# Mini-RS485_RJ45-MySens-v05.net
KiCad netlist of a schematic drawn in EAGLE
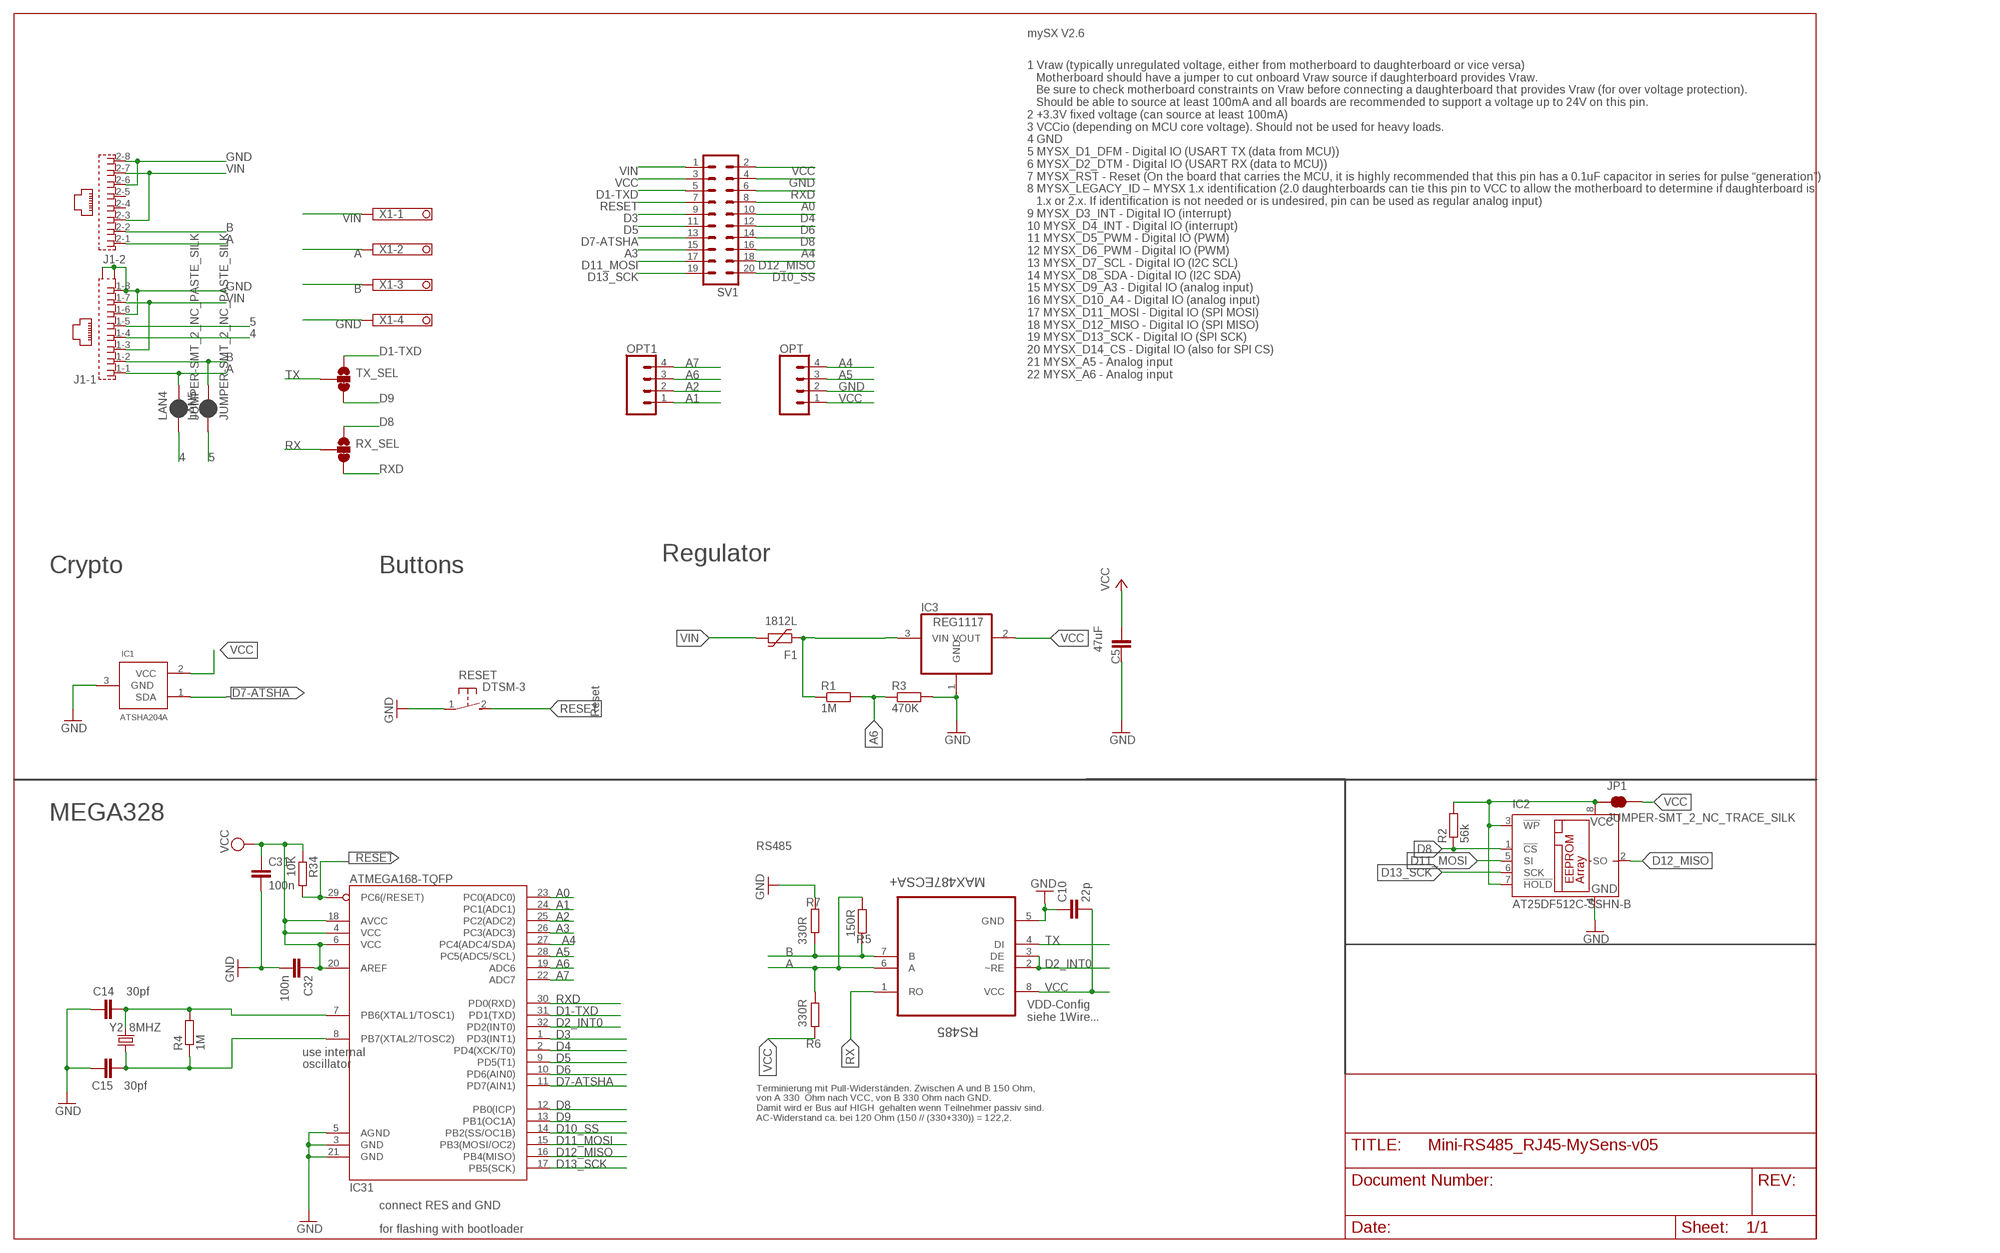
[diagram p0: schematic, sheet 1]

(export (version "E")
  (design (tool "Eeschema 10.0.6"))
  (components
    (comp (ref "C5")
      (value "47uF")
      (footprint "eagle-import:C1210")
      (libsource (lib "eagle-import") (part "C-EUC1210"))
    )
    (comp (ref "C10")
      (value "22p")
      (footprint "eagle-import:C0805")
      (libsource (lib "eagle-import") (part "C-EUC0805"))
    )
    (comp (ref "C14")
      (value "30pf")
      (footprint "eagle-import:0805")
      (libsource (lib "eagle-import") (part "CAP0805"))
    )
    (comp (ref "C15")
      (value "30pf")
      (footprint "eagle-import:0805")
      (libsource (lib "eagle-import") (part "CAP0805"))
    )
    (comp (ref "C31")
      (value "100n")
      (footprint "eagle-import:C0805")
      (libsource (lib "eagle-import") (part "C-EUC0805"))
    )
    (comp (ref "C32")
      (value "100n")
      (footprint "eagle-import:C0805")
      (libsource (lib "eagle-import") (part "C-EUC0805"))
    )
    (comp (ref "F1")
      (value "1812L")
      (footprint "eagle-import:1812L")
      (libsource (lib "eagle-import") (part "1812L"))
    )
    (comp (ref "IC1")
      (value "ATSHA204A")
      (footprint "eagle-import:SOT23")
      (libsource (lib "eagle-import") (part "ATSHA204A"))
    )
    (comp (ref "IC2")
      (value "AT25DF512C-SSHN-B")
      (footprint "eagle-import:SO-08")
      (fields (field (name "MF") "MICROCHIP") (field (name "MPN") "25AA080/SN"))
      (libsource (lib "eagle-import") (part "25SNAA080"))
    )
    (comp (ref "IC3")
      (value "REG1117")
      (footprint "eagle-import:SOT223")
      (libsource (lib "eagle-import") (part "REG1117"))
    )
    (comp (ref "IC31")
      (value "ATMEGA168-TQFP")
      (footprint "eagle-import:TQFP32-08")
      (libsource (lib "eagle-import") (part "ATMEGA168-TQFP"))
    )
    (comp (ref "J1")
      (value "RJ45_2X_NARROW_SHILDPINS")
      (footprint "eagle-import:RJ45_2X_NARROW_SHILDPINS")
      (libsource (lib "eagle-import") (part "RJ45_2X_NARROW_SHILDPINS"))
    )
    (comp (ref "JP1")
      (value "JUMPER-SMT_2_NC_TRACE_SILK")
      (footprint "eagle-import:SMT-JUMPER_2_NC_TRACE_SILK")
      (libsource (lib "eagle-import") (part "JUMPER-SMT_2_NC_TRACE_SILK"))
    )
    (comp (ref "LAN4")
      (value "JUMPER-SMT_2_NC_PASTE_SILK")
      (footprint "eagle-import:SMT-JUMPER_2_NC_PASTE_SILK")
      (libsource (lib "eagle-import") (part "JUMPER-SMT_2_NC_PASTE_SILK"))
    )
    (comp (ref "LAN5")
      (value "JUMPER-SMT_2_NC_PASTE_SILK")
      (footprint "eagle-import:SMT-JUMPER_2_NC_PASTE_SILK")
      (libsource (lib "eagle-import") (part "JUMPER-SMT_2_NC_PASTE_SILK"))
    )
    (comp (ref "OPT")
      (value "CONN_04")
      (footprint "eagle-import:1X04")
      (libsource (lib "eagle-import") (part "CONN_04"))
    )
    (comp (ref "OPT1")
      (value "CONN_04")
      (footprint "eagle-import:1X04")
      (libsource (lib "eagle-import") (part "CONN_04"))
    )
    (comp (ref "R1")
      (value "1M")
      (footprint "eagle-import:M0805")
      (libsource (lib "eagle-import") (part "R-EU_M0805"))
    )
    (comp (ref "R2")
      (value "56k")
      (footprint "eagle-import:M0805")
      (libsource (lib "eagle-import") (part "resistor_R-EU_M0805"))
    )
    (comp (ref "R3")
      (value "470K")
      (footprint "eagle-import:R0805")
      (libsource (lib "eagle-import") (part "R-EU_R0805"))
    )
    (comp (ref "R4")
      (value "1M")
      (footprint "eagle-import:M0805")
      (libsource (lib "eagle-import") (part "R-EU_M0805"))
    )
    (comp (ref "R5")
      (value "150R")
      (footprint "eagle-import:R0805")
      (libsource (lib "eagle-import") (part "R-EU_R0805"))
    )
    (comp (ref "R6")
      (value "330R")
      (footprint "eagle-import:R0805")
      (libsource (lib "eagle-import") (part "R-EU_R0805"))
    )
    (comp (ref "R7")
      (value "330R")
      (footprint "eagle-import:R0805")
      (libsource (lib "eagle-import") (part "R-EU_R0805"))
    )
    (comp (ref "R34")
      (value "10K")
      (footprint "eagle-import:R0805")
      (libsource (lib "eagle-import") (part "R-EU_R0805"))
    )
    (comp (ref "RESET")
      (value "DTSM-3")
      (footprint "eagle-import:DTSM-3")
      (libsource (lib "eagle-import") (part "DTSM-3"))
    )
    (comp (ref "RS485")
      (value "MAX487ECSA+")
      (footprint "eagle-import:SOIC127P600X175-8N")
      (libsource (lib "eagle-import") (part "MAX487ECSA+"))
    )
    (comp (ref "RX_SEL")
      (value "JUMPER-SMT_3_1-NC_TRACE_SILK")
      (footprint "eagle-import:SMT-JUMPER_3_1-NC_TRACE_SILK")
      (libsource (lib "eagle-import") (part "JUMPER-SMT_3_1-NC_TRACE_SILK"))
    )
    (comp (ref "SV1")
      (value "MA10-2")
      (footprint "eagle-import:MA10-2")
      (libsource (lib "eagle-import") (part "MA10-2"))
    )
    (comp (ref "TX_SEL")
      (value "JUMPER-SMT_3_1-NC_TRACE_SILK")
      (footprint "eagle-import:SMT-JUMPER_3_1-NC_TRACE_SILK")
      (libsource (lib "eagle-import") (part "JUMPER-SMT_3_1-NC_TRACE_SILK"))
    )
    (comp (ref "X1")
      (value "1751264")
      (footprint "eagle-import:1751264")
      (libsource (lib "eagle-import") (part "1751264"))
    )
    (comp (ref "Y2")
      (value "8MHZ")
      (footprint "eagle-import:CRYSTAL-TXC-7A")
      (libsource (lib "eagle-import") (part "CRYSTALTXC-7A"))
    )
  )
  (nets
    (net (code "1") (name "/4") (class "Default")
      (node (ref "J1") (pin "1-4") (pinfunction "4_1-4") (pintype "passive"))
      (node (ref "LAN4") (pin "1") (pinfunction "1_1") (pintype "passive"))
    )
    (net (code "2") (name "/5") (class "Default")
      (node (ref "J1") (pin "1-5") (pinfunction "5_1-5") (pintype "passive"))
      (node (ref "LAN5") (pin "1") (pinfunction "1_1") (pintype "passive"))
    )
    (net (code "3") (name "/A") (class "Default")
      (node (ref "J1") (pin "1-1") (pinfunction "1_1-1") (pintype "passive"))
      (node (ref "J1") (pin "2-1") (pinfunction "1_2-1") (pintype "passive"))
      (node (ref "LAN4") (pin "2") (pinfunction "2_2") (pintype "passive"))
      (node (ref "R5") (pin "1") (pinfunction "1_1") (pintype "passive"))
      (node (ref "R6") (pin "2") (pinfunction "2_2") (pintype "passive"))
      (node (ref "RS485") (pin "6") (pinfunction "A_6") (pintype "bidirectional"))
      (node (ref "X1") (pin "2") (pinfunction "K_2") (pintype "passive"))
    )
    (net (code "4") (name "/A0") (class "Default")
      (node (ref "IC31") (pin "23") (pinfunction "PC0(ADC0)_23") (pintype "bidirectional"))
      (node (ref "SV1") (pin "8") (pinfunction "8_8") (pintype "passive"))
    )
    (net (code "5") (name "/A1") (class "Default")
      (node (ref "IC31") (pin "24") (pinfunction "PC1(ADC1)_24") (pintype "bidirectional"))
      (node (ref "OPT1") (pin "1") (pinfunction "1_1") (pintype "passive"))
    )
    (net (code "6") (name "/A2") (class "Default")
      (node (ref "IC31") (pin "25") (pinfunction "PC2(ADC2)_25") (pintype "bidirectional"))
      (node (ref "OPT1") (pin "2") (pinfunction "2_2") (pintype "passive"))
    )
    (net (code "7") (name "/A3") (class "Default")
      (node (ref "IC31") (pin "26") (pinfunction "PC3(ADC3)_26") (pintype "bidirectional"))
      (node (ref "SV1") (pin "15") (pinfunction "15_15") (pintype "passive"))
    )
    (net (code "8") (name "/A4") (class "Default")
      (node (ref "IC31") (pin "27") (pinfunction "PC4(ADC4/SDA)_27") (pintype "bidirectional"))
      (node (ref "OPT") (pin "4") (pinfunction "4_4") (pintype "passive"))
      (node (ref "SV1") (pin "16") (pinfunction "16_16") (pintype "passive"))
    )
    (net (code "9") (name "/A5") (class "Default")
      (node (ref "IC31") (pin "28") (pinfunction "PC5(ADC5/SCL)_28") (pintype "bidirectional"))
      (node (ref "OPT") (pin "3") (pinfunction "3_3") (pintype "passive"))
    )
    (net (code "10") (name "/A7") (class "Default")
      (node (ref "IC31") (pin "22") (pinfunction "ADC7_22") (pintype "bidirectional"))
      (node (ref "OPT1") (pin "4") (pinfunction "4_4") (pintype "passive"))
    )
    (net (code "11") (name "/B") (class "Default")
      (node (ref "J1") (pin "1-2") (pinfunction "2_1-2") (pintype "passive"))
      (node (ref "J1") (pin "2-2") (pinfunction "2_2-2") (pintype "passive"))
      (node (ref "LAN5") (pin "2") (pinfunction "2_2") (pintype "passive"))
      (node (ref "R5") (pin "2") (pinfunction "2_2") (pintype "passive"))
      (node (ref "R7") (pin "1") (pinfunction "1_1") (pintype "passive"))
      (node (ref "RS485") (pin "7") (pinfunction "B_7") (pintype "bidirectional"))
      (node (ref "X1") (pin "3") (pinfunction "K_3") (pintype "passive"))
    )
    (net (code "12") (name "/D1-TXD") (class "Default")
      (node (ref "IC31") (pin "31") (pinfunction "PD1(TXD)_31") (pintype "bidirectional"))
      (node (ref "SV1") (pin "5") (pinfunction "5_5") (pintype "passive"))
      (node (ref "TX_SEL") (pin "1") (pinfunction "1_1") (pintype "passive"))
    )
    (net (code "13") (name "/D2_INT0") (class "Default")
      (node (ref "IC31") (pin "32") (pinfunction "PD2(INT0)_32") (pintype "bidirectional"))
      (node (ref "RS485") (pin "2") (pinfunction "~{RE}_2") (pintype "input"))
      (node (ref "RS485") (pin "3") (pinfunction "DE_3") (pintype "input"))
    )
    (net (code "14") (name "/D3") (class "Default")
      (node (ref "IC31") (pin "1") (pinfunction "PD3(INT1)_1") (pintype "bidirectional"))
      (node (ref "SV1") (pin "9") (pinfunction "9_9") (pintype "passive"))
    )
    (net (code "15") (name "/D4") (class "Default")
      (node (ref "IC31") (pin "2") (pinfunction "PD4(XCK/T0)_2") (pintype "bidirectional"))
      (node (ref "SV1") (pin "10") (pinfunction "10_10") (pintype "passive"))
    )
    (net (code "16") (name "/D5") (class "Default")
      (node (ref "IC31") (pin "9") (pinfunction "PD5(T1)_9") (pintype "bidirectional"))
      (node (ref "SV1") (pin "11") (pinfunction "11_11") (pintype "passive"))
    )
    (net (code "17") (name "/D6") (class "Default")
      (node (ref "IC31") (pin "10") (pinfunction "PD6(AIN0)_10") (pintype "bidirectional"))
      (node (ref "SV1") (pin "12") (pinfunction "12_12") (pintype "passive"))
    )
    (net (code "18") (name "/D7-ATSHA") (class "Default")
      (node (ref "IC1") (pin "1") (pinfunction "SDA_1") (pintype "bidirectional"))
      (node (ref "IC31") (pin "11") (pinfunction "PD7(AIN1)_11") (pintype "bidirectional"))
      (node (ref "SV1") (pin "13") (pinfunction "13_13") (pintype "passive"))
    )
    (net (code "19") (name "/D9") (class "Default")
      (node (ref "IC31") (pin "13") (pinfunction "PB1(OC1A)_13") (pintype "bidirectional"))
      (node (ref "TX_SEL") (pin "3") (pinfunction "3_3") (pintype "passive"))
    )
    (net (code "20") (name "/D10_SS") (class "Default")
      (node (ref "IC31") (pin "14") (pinfunction "PB2(SS/OC1B)_14") (pintype "bidirectional"))
      (node (ref "SV1") (pin "20") (pinfunction "20_20") (pintype "passive"))
    )
    (net (code "21") (name "/RXD") (class "Default")
      (node (ref "IC31") (pin "30") (pinfunction "PD0(RXD)_30") (pintype "bidirectional"))
      (node (ref "RX_SEL") (pin "3") (pinfunction "3_3") (pintype "passive"))
      (node (ref "SV1") (pin "6") (pinfunction "6_6") (pintype "passive"))
    )
    (net (code "22") (name "/TX") (class "Default")
      (node (ref "RS485") (pin "4") (pinfunction "DI_4") (pintype "input"))
      (node (ref "TX_SEL") (pin "2") (pinfunction "2_2") (pintype "passive"))
    )
    (net (code "23") (name "A6") (class "Default")
      (node (ref "IC31") (pin "19") (pinfunction "ADC6_19") (pintype "bidirectional"))
      (node (ref "OPT1") (pin "3") (pinfunction "3_3") (pintype "passive"))
      (node (ref "R1") (pin "2") (pinfunction "2_2") (pintype "passive"))
      (node (ref "R3") (pin "1") (pinfunction "1_1") (pintype "passive"))
    )
    (net (code "24") (name "D8") (class "Default")
      (node (ref "IC2") (pin "1") (pinfunction "~{CS}_1") (pintype "input"))
      (node (ref "IC31") (pin "12") (pinfunction "PB0(ICP)_12") (pintype "bidirectional"))
      (node (ref "R2") (pin "1") (pinfunction "1_1") (pintype "passive"))
      (node (ref "RX_SEL") (pin "1") (pinfunction "1_1") (pintype "passive"))
      (node (ref "SV1") (pin "14") (pinfunction "14_14") (pintype "passive"))
    )
    (net (code "25") (name "D11_MOSI") (class "Default")
      (node (ref "IC2") (pin "5") (pinfunction "SI_5") (pintype "input"))
      (node (ref "IC31") (pin "15") (pinfunction "PB3(MOSI/OC2)_15") (pintype "bidirectional"))
      (node (ref "SV1") (pin "17") (pinfunction "17_17") (pintype "passive"))
    )
    (net (code "26") (name "D12_MISO") (class "Default")
      (node (ref "IC2") (pin "2") (pinfunction "SO_2") (pintype "bidirectional"))
      (node (ref "IC31") (pin "16") (pinfunction "PB4(MISO)_16") (pintype "bidirectional"))
      (node (ref "SV1") (pin "18") (pinfunction "18_18") (pintype "passive"))
    )
    (net (code "27") (name "D13_SCK") (class "Default")
      (node (ref "IC2") (pin "6") (pinfunction "SCK_6") (pintype "input"))
      (node (ref "IC31") (pin "17") (pinfunction "PB5(SCK)_17") (pintype "bidirectional"))
      (node (ref "SV1") (pin "19") (pinfunction "19_19") (pintype "passive"))
    )
    (net (code "28") (name "GND") (class "Default")
      (node (ref "C10") (pin "1") (pinfunction "1_1") (pintype "passive"))
      (node (ref "C14") (pin "1") (pinfunction "1_1") (pintype "passive"))
      (node (ref "C15") (pin "1") (pinfunction "1_1") (pintype "passive"))
      (node (ref "C31") (pin "2") (pinfunction "2_2") (pintype "passive"))
      (node (ref "C32") (pin "2") (pinfunction "2_2") (pintype "passive"))
      (node (ref "C5") (pin "1") (pinfunction "1_1") (pintype "passive"))
      (node (ref "IC1") (pin "3") (pinfunction "GND_3") (pintype "bidirectional"))
      (node (ref "IC2") (pin "4") (pinfunction "GND_4") (pintype "power_in"))
      (node (ref "IC3") (pin "1") (pinfunction "GND_1") (pintype "power_in"))
      (node (ref "IC31") (pin "21") (pinfunction "GND_21") (pintype "bidirectional"))
      (node (ref "IC31") (pin "3") (pinfunction "GND_3") (pintype "bidirectional"))
      (node (ref "IC31") (pin "5") (pinfunction "AGND_5") (pintype "bidirectional"))
      (node (ref "J1") (pin "1-6") (pinfunction "6_1-6") (pintype "passive"))
      (node (ref "J1") (pin "1-8") (pinfunction "8_1-8") (pintype "passive"))
      (node (ref "J1") (pin "2-6") (pinfunction "6_2-6") (pintype "passive"))
      (node (ref "J1") (pin "2-8") (pinfunction "8_2-8") (pintype "passive"))
      (node (ref "J1") (pin "G1") (pinfunction "S1_G1") (pintype "passive"))
      (node (ref "J1") (pin "G3") (pinfunction "S2_G3") (pintype "passive"))
      (node (ref "OPT") (pin "2") (pinfunction "2_2") (pintype "passive"))
      (node (ref "R3") (pin "2") (pinfunction "2_2") (pintype "passive"))
      (node (ref "R7") (pin "2") (pinfunction "2_2") (pintype "passive"))
      (node (ref "RESET") (pin "1") (pinfunction "1_1") (pintype "passive"))
      (node (ref "RS485") (pin "5") (pinfunction "GND_5") (pintype "passive"))
      (node (ref "SV1") (pin "4") (pinfunction "4_4") (pintype "passive"))
      (node (ref "X1") (pin "4") (pinfunction "K_4") (pintype "passive"))
    )
    (net (code "29") (name "Net-(F1-1)") (class "Default")
      (node (ref "F1") (pin "P$1") (pinfunction "1_P$1") (pintype "passive"))
      (node (ref "IC3") (pin "3") (pinfunction "VIN_3") (pintype "input"))
      (node (ref "R1") (pin "1") (pinfunction "1_1") (pintype "passive"))
    )
    (net (code "30") (name "Net-(IC2-VCC)") (class "Default")
      (node (ref "IC2") (pin "3") (pinfunction "~{WP}_3") (pintype "input"))
      (node (ref "IC2") (pin "7") (pinfunction "~{HOLD}_7") (pintype "input"))
      (node (ref "IC2") (pin "8") (pinfunction "VCC_8") (pintype "power_in"))
      (node (ref "JP1") (pin "1") (pinfunction "1_1") (pintype "passive"))
      (node (ref "R2") (pin "2") (pinfunction "2_2") (pintype "passive"))
    )
    (net (code "31") (name "Net-(IC31-PB6(XTAL1{slash}TOSC1))") (class "Default")
      (node (ref "C14") (pin "2") (pinfunction "2_2") (pintype "passive"))
      (node (ref "IC31") (pin "7") (pinfunction "PB6(XTAL1/TOSC1)_7") (pintype "bidirectional"))
      (node (ref "R4") (pin "2") (pinfunction "2_2") (pintype "passive"))
      (node (ref "Y2") (pin "P$2") (pinfunction "2_P$2") (pintype "passive"))
    )
    (net (code "32") (name "Net-(IC31-PB7(XTAL2{slash}TOSC2))") (class "Default")
      (node (ref "C15") (pin "2") (pinfunction "2_2") (pintype "passive"))
      (node (ref "IC31") (pin "8") (pinfunction "PB7(XTAL2/TOSC2)_8") (pintype "bidirectional"))
      (node (ref "R4") (pin "1") (pinfunction "1_1") (pintype "passive"))
      (node (ref "Y2") (pin "P$1") (pinfunction "1_P$1") (pintype "passive"))
    )
    (net (code "33") (name "RESET") (class "Default")
      (node (ref "IC31") (pin "29") (pinfunction "PC6(/RESET)_29") (pintype "bidirectional"))
      (node (ref "R34") (pin "2") (pinfunction "2_2") (pintype "passive"))
      (node (ref "RESET") (pin "2") (pinfunction "2_2") (pintype "passive"))
      (node (ref "SV1") (pin "7") (pinfunction "7_7") (pintype "passive"))
    )
    (net (code "34") (name "RX") (class "Default")
      (node (ref "RS485") (pin "1") (pinfunction "RO_1") (pintype "output"))
      (node (ref "RX_SEL") (pin "2") (pinfunction "2_2") (pintype "passive"))
    )
    (net (code "35") (name "VCC") (class "Default")
      (node (ref "C10") (pin "2") (pinfunction "2_2") (pintype "passive"))
      (node (ref "C31") (pin "1") (pinfunction "1_1") (pintype "passive"))
      (node (ref "C32") (pin "1") (pinfunction "1_1") (pintype "passive"))
      (node (ref "C5") (pin "2") (pinfunction "2_2") (pintype "passive"))
      (node (ref "IC1") (pin "2") (pinfunction "VCC_2") (pintype "bidirectional"))
      (node (ref "IC3") (pin "2") (pinfunction "VOUT_2") (pintype "output"))
      (node (ref "IC31") (pin "18") (pinfunction "AVCC_18") (pintype "bidirectional"))
      (node (ref "IC31") (pin "20") (pinfunction "AREF_20") (pintype "bidirectional"))
      (node (ref "IC31") (pin "4") (pinfunction "VCC_4") (pintype "bidirectional"))
      (node (ref "IC31") (pin "6") (pinfunction "VCC_6") (pintype "bidirectional"))
      (node (ref "JP1") (pin "2") (pinfunction "2_2") (pintype "passive"))
      (node (ref "OPT") (pin "1") (pinfunction "1_1") (pintype "passive"))
      (node (ref "R34") (pin "1") (pinfunction "1_1") (pintype "passive"))
      (node (ref "R6") (pin "1") (pinfunction "1_1") (pintype "passive"))
      (node (ref "RS485") (pin "8") (pinfunction "VCC_8") (pintype "power_in"))
      (node (ref "SV1") (pin "2") (pinfunction "2_2") (pintype "passive"))
      (node (ref "SV1") (pin "3") (pinfunction "3_3") (pintype "passive"))
    )
    (net (code "36") (name "VIN") (class "Default")
      (node (ref "F1") (pin "P$2") (pinfunction "2_P$2") (pintype "passive"))
      (node (ref "J1") (pin "1-3") (pinfunction "3_1-3") (pintype "passive"))
      (node (ref "J1") (pin "1-7") (pinfunction "7_1-7") (pintype "passive"))
      (node (ref "J1") (pin "2-3") (pinfunction "3_2-3") (pintype "passive"))
      (node (ref "J1") (pin "2-7") (pinfunction "7_2-7") (pintype "passive"))
      (node (ref "SV1") (pin "1") (pinfunction "1_1") (pintype "passive"))
      (node (ref "X1") (pin "1") (pinfunction "K_1") (pintype "passive"))
    )
    (net (code "37") (name "unconnected-(J1B-4-Pad2-4)") (class "Default")
      (node (ref "J1") (pin "2-4") (pinfunction "4_2-4") (pintype "passive"))
    )
    (net (code "38") (name "unconnected-(J1B-5-Pad2-5)") (class "Default")
      (node (ref "J1") (pin "2-5") (pinfunction "5_2-5") (pintype "passive"))
    )
  )
)
